# V_1.net
KiCad netlist of a schematic drawn in EAGLE
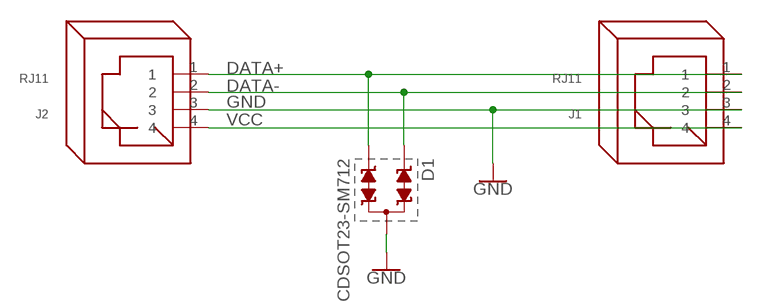
[diagram p0: schematic, sheet 1]

(export (version "E")
  (design (tool "Eeschema 10.0.6"))
  (components
    (comp (ref "D1")
      (value "CDSOT23-SM712")
      (footprint "eagle-import:SOT23")
      (libsource (lib "eagle-import") (part "CDSOT23-SM712"))
    )
    (comp (ref "J1")
      (value "RJ11")
      (footprint "eagle-import:RJ11")
      (libsource (lib "eagle-import") (part "RJ11"))
    )
    (comp (ref "J2")
      (value "RJ11")
      (footprint "eagle-import:RJ11")
      (libsource (lib "eagle-import") (part "RJ11"))
    )
  )
  (nets
    (net (code "1") (name "/DATA+") (class "Default")
      (node (ref "D1") (pin "2") (pinfunction "2_2") (pintype "passive"))
      (node (ref "J1") (pin "1") (pinfunction "1_1") (pintype "bidirectional"))
      (node (ref "J2") (pin "1") (pinfunction "1_1") (pintype "bidirectional"))
    )
    (net (code "2") (name "/DATA-") (class "Default")
      (node (ref "D1") (pin "1") (pinfunction "1_1") (pintype "passive"))
      (node (ref "J1") (pin "2") (pinfunction "2_2") (pintype "bidirectional"))
      (node (ref "J2") (pin "2") (pinfunction "2_2") (pintype "bidirectional"))
    )
    (net (code "3") (name "/VCC") (class "Default")
      (node (ref "J1") (pin "4") (pinfunction "4_4") (pintype "bidirectional"))
      (node (ref "J2") (pin "4") (pinfunction "4_4") (pintype "bidirectional"))
    )
    (net (code "4") (name "GND") (class "Default")
      (node (ref "D1") (pin "3") (pinfunction "3_3") (pintype "passive"))
      (node (ref "J1") (pin "3") (pinfunction "3_3") (pintype "bidirectional"))
      (node (ref "J2") (pin "3") (pinfunction "3_3") (pintype "bidirectional"))
    )
  )
)
